# usb_uart.net
KiCad netlist of a schematic drawn in Altium Designer
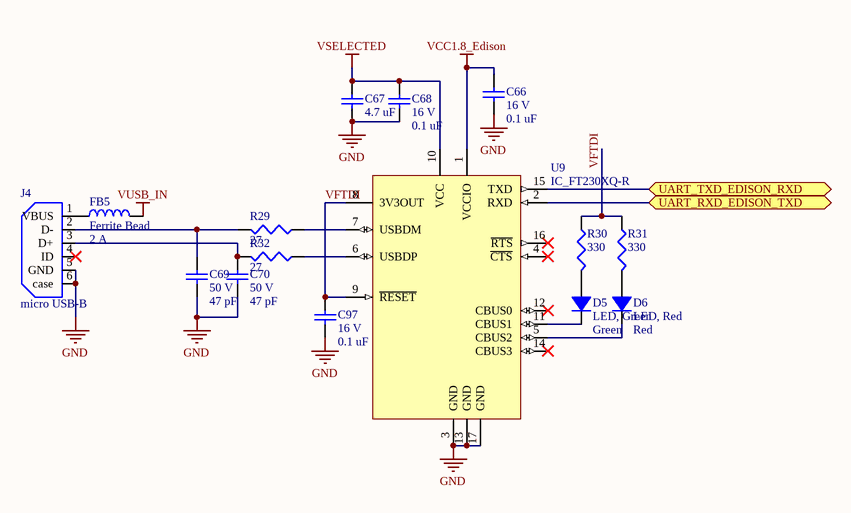
[diagram p0: usb_uart.SchDoc]

(export (version "E")
  (design (tool "Eeschema 10.0.6"))
  (components
    (comp (ref "C66")
      (value "0.1 uF")
      (footprint "0402")
      (description "Ceramic capacitor, 0.1u, 16 V, 0402 package")
      (fields
        (field (name "TOLERANCE") "10%")
        (field (name "VOLTAGE RATED") "16 V")
        (field (name "Comment") "Ceramic capacitor")
      )
      (libsource (lib "rlc") (part "C_0.1u_16V_0402_ceramic"))
    )
    (comp (ref "C67")
      (value "4.7 uF")
      (footprint "0603")
      (description "Ceramic capacitor, 4.7u, 10V, 0603 package")
      (fields (field (name "TOLERANCE") "20%") (field (name "Comment") "Ceramic capacitor"))
      (libsource (lib "rlc") (part "C_4.7u_10V_0603_ceramic"))
    )
    (comp (ref "C68")
      (value "0.1 uF")
      (footprint "0402")
      (description "Ceramic capacitor, 0.1u, 16 V, 0402 package")
      (fields
        (field (name "TOLERANCE") "10%")
        (field (name "VOLTAGE RATED") "16 V")
        (field (name "Comment") "Ceramic capacitor")
      )
      (libsource (lib "rlc") (part "C_0.1u_16V_0402_ceramic"))
    )
    (comp (ref "C69")
      (value "47 pF")
      (footprint "0402")
      (description "Ceramic capacitor, 47 pF, 0402 package")
      (fields
        (field (name "TOLERANCE") "5%")
        (field (name "VOLTAGE RATED") "50 V")
        (field (name "Comment") "Ceramic capacitor")
      )
      (libsource (lib "rlc") (part "C_47p_50V_0402_ceramic"))
    )
    (comp (ref "C70")
      (value "47 pF")
      (footprint "0402")
      (description "Ceramic capacitor, 47 pF, 0402 package")
      (fields
        (field (name "TOLERANCE") "5%")
        (field (name "VOLTAGE RATED") "50 V")
        (field (name "Comment") "Ceramic capacitor")
      )
      (libsource (lib "rlc") (part "C_47p_50V_0402_ceramic"))
    )
    (comp (ref "C97")
      (value "0.1 uF")
      (footprint "0402")
      (description "Ceramic capacitor, 0.1u, 16 V, 0402 package")
      (fields
        (field (name "TOLERANCE") "10%")
        (field (name "VOLTAGE RATED") "16 V")
        (field (name "Comment") "Ceramic capacitor")
      )
      (libsource (lib "rlc") (part "C_0.1u_16V_0402_ceramic"))
    )
    (comp (ref "D5")
      (value "LED, Green")
      (footprint "0402 - DIODE")
      (description "LED, Green,  0402")
      (fields (field (name "COLOR") "Green"))
      (libsource (lib "rlc") (part "D_LED_GREEN_0402"))
    )
    (comp (ref "D6")
      (value "LED, Red")
      (footprint "0402 - DIODE")
      (description "LED, Red, 0402")
      (fields (field (name "COLOR") "Red"))
      (libsource (lib "rlc") (part "D_LED_RED_0402"))
    )
    (comp (ref "FB5")
      (value "Ferrite Bead")
      (footprint "0603")
      (description "Ferrite Bead, 2 A, 0603 package")
      (fields (field (name "CURRENT RATING") "2 A"))
      (libsource (lib "rlc") (part "FB_2A_0603"))
    )
    (comp (ref "J4")
      (value "micro USB-B")
      (footprint "Micro USB-B")
      (description "CONN USB MICRO B RECPT SMT R/A")
      (libsource (lib "connectors") (part "Micro USB"))
    )
    (comp (ref "R29")
      (value "27")
      (footprint "0402")
      (description "Chip resistor, 27, 0402 package")
      (fields (field (name "TOLERANCE") "1%") (field (name "POWER") "1/16 W"))
      (libsource (lib "rlc") (part "R_27_0402"))
    )
    (comp (ref "R30")
      (value "330")
      (footprint "0402")
      (description "Chip resistor, 330, 0402 package")
      (fields (field (name "TOLERANCE") "1%") (field (name "POWER") "1/16 W"))
      (libsource (lib "rlc") (part "R_330_0402"))
    )
    (comp (ref "R31")
      (value "330")
      (footprint "0402")
      (description "Chip resistor, 330, 0402 package")
      (fields (field (name "TOLERANCE") "1%") (field (name "POWER") "1/16 W"))
      (libsource (lib "rlc") (part "R_330_0402"))
    )
    (comp (ref "R32")
      (value "27")
      (footprint "0402")
      (description "Chip resistor, 27, 0402 package")
      (fields (field (name "TOLERANCE") "1%") (field (name "POWER") "1/16 W"))
      (libsource (lib "rlc") (part "R_27_0402"))
    )
    (comp (ref "U9")
      (value "IC_FT230XQ-R")
      (footprint "QFN-16")
      (description "FT230X USB UART")
      (libsource (lib "FTDI_SCH_Public") (part "IC_FT230XQ-R"))
    )
  )
  (nets
    (net (code "1") (name "/UART_RXD_EDISON_TXD") (class "Default")
      (node (ref "U9") (pin "2") (pinfunction "RXD_2") (pintype "input"))
    )
    (net (code "2") (name "/UART_TXD_EDISON_RXD") (class "Default")
      (node (ref "U9") (pin "15") (pinfunction "TXD_15") (pintype "output"))
    )
    (net (code "3") (name "/VFTDI") (class "Default")
      (node (ref "C97") (pin "1") (pintype "passive"))
      (node (ref "R30") (pin "2") (pintype "passive"))
      (node (ref "R31") (pin "2") (pintype "passive"))
      (node (ref "U9") (pin "8") (pinfunction "3V3OUT_8") (pintype "passive"))
      (node (ref "U9") (pin "9") (pinfunction "~{RESET}_9") (pintype "input"))
    )
    (net (code "4") (name "GND") (class "Default")
      (node (ref "C66") (pin "2") (pintype "passive"))
      (node (ref "C67") (pin "2") (pintype "passive"))
      (node (ref "C68") (pin "2") (pintype "passive"))
      (node (ref "C69") (pin "2") (pintype "passive"))
      (node (ref "C70") (pin "2") (pintype "passive"))
      (node (ref "C97") (pin "2") (pintype "passive"))
      (node (ref "J4") (pin "5") (pinfunction "GND_5") (pintype "power_in"))
      (node (ref "J4") (pin "6") (pinfunction "case_6") (pintype "power_in"))
      (node (ref "U9") (pin "13") (pinfunction "GND_13") (pintype "passive"))
      (node (ref "U9") (pin "17") (pinfunction "GND_17") (pintype "passive"))
      (node (ref "U9") (pin "3") (pinfunction "GND_3") (pintype "passive"))
    )
    (net (code "5") (name "Net-(D5-Pad1)") (class "Default")
      (node (ref "D5") (pin "1") (pintype "passive"))
      (node (ref "R30") (pin "1") (pintype "passive"))
    )
    (net (code "6") (name "Net-(D6-Pad1)") (class "Default")
      (node (ref "D6") (pin "1") (pintype "passive"))
      (node (ref "R31") (pin "1") (pintype "passive"))
    )
    (net (code "7") (name "Net-(J4-D+)") (class "Default")
      (node (ref "C70") (pin "1") (pintype "passive"))
      (node (ref "J4") (pin "3") (pinfunction "D+_3") (pintype "power_in"))
      (node (ref "R32") (pin "1") (pintype "passive"))
    )
    (net (code "8") (name "Net-(J4-D-)") (class "Default")
      (node (ref "C69") (pin "1") (pintype "passive"))
      (node (ref "J4") (pin "2") (pinfunction "D-_2") (pintype "power_in"))
      (node (ref "R29") (pin "1") (pintype "passive"))
    )
    (net (code "9") (name "Net-(J4-VBUS)") (class "Default")
      (node (ref "FB5") (pin "2") (pintype "passive"))
      (node (ref "J4") (pin "1") (pinfunction "VBUS_1") (pintype "power_in"))
    )
    (net (code "10") (name "Net-(U9-CBUS1)") (class "Default")
      (node (ref "D5") (pin "2") (pintype "passive"))
      (node (ref "U9") (pin "11") (pinfunction "CBUS1_11") (pintype "bidirectional"))
    )
    (net (code "11") (name "Net-(U9-CBUS2)") (class "Default")
      (node (ref "D6") (pin "2") (pintype "passive"))
      (node (ref "U9") (pin "5") (pinfunction "CBUS2_5") (pintype "bidirectional"))
    )
    (net (code "12") (name "Net-(U9-USBDM)") (class "Default")
      (node (ref "R29") (pin "2") (pintype "passive"))
      (node (ref "U9") (pin "7") (pinfunction "USBDM_7") (pintype "bidirectional"))
    )
    (net (code "13") (name "Net-(U9-USBDP)") (class "Default")
      (node (ref "R32") (pin "2") (pintype "passive"))
      (node (ref "U9") (pin "6") (pinfunction "USBDP_6") (pintype "bidirectional"))
    )
    (net (code "14") (name "VCC1.8_Edison") (class "Default")
      (node (ref "C66") (pin "1") (pintype "passive"))
      (node (ref "U9") (pin "1") (pinfunction "VCCIO_1") (pintype "passive"))
    )
    (net (code "15") (name "VSELECTED") (class "Default")
      (node (ref "C67") (pin "1") (pintype "passive"))
      (node (ref "C68") (pin "1") (pintype "passive"))
      (node (ref "U9") (pin "10") (pinfunction "VCC_10") (pintype "passive"))
    )
    (net (code "16") (name "VUSB_IN") (class "Default") (node (ref "FB5") (pin "1") (pintype "passive")))
    (net (code "17") (name "unconnected-(J4-ID-Pad4)") (class "Default")
      (node (ref "J4") (pin "4") (pinfunction "ID_4") (pintype "power_in+no_connect"))
    )
    (net (code "18") (name "unconnected-(U9-CBUS0-Pad12)") (class "Default")
      (node (ref "U9") (pin "12") (pinfunction "CBUS0_12") (pintype "bidirectional+no_connect"))
    )
    (net (code "19") (name "unconnected-(U9-CBUS3-Pad14)") (class "Default")
      (node (ref "U9") (pin "14") (pinfunction "CBUS3_14") (pintype "bidirectional+no_connect"))
    )
    (net (code "20") (name "unconnected-(U9-~{CTS}-Pad4)") (class "Default")
      (node (ref "U9") (pin "4") (pinfunction "~{CTS}_4") (pintype "input+no_connect"))
    )
    (net (code "21") (name "unconnected-(U9-~{RTS}-Pad16)") (class "Default")
      (node (ref "U9") (pin "16") (pinfunction "~{RTS}_16") (pintype "output+no_connect"))
    )
  )
)
